# ad_1.net
KiCad netlist of a schematic drawn in Altium Designer
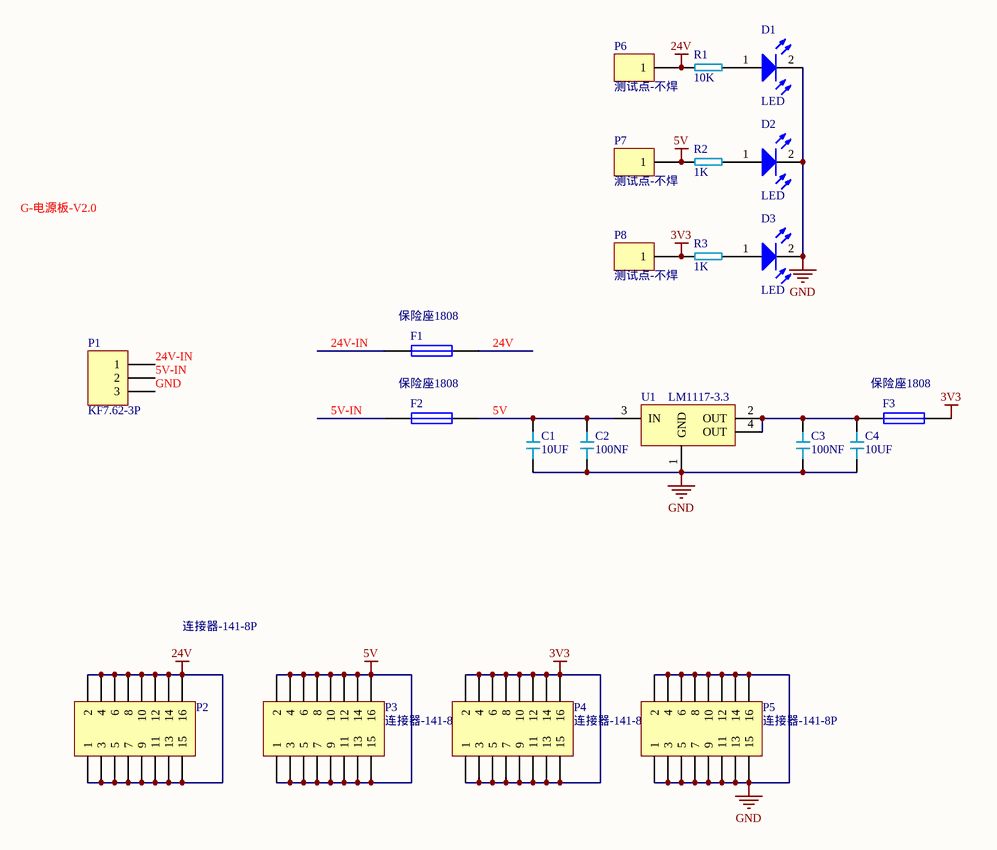
[diagram p0: ad_1.schdoc]

(export (version "E")
  (design (tool "Eeschema 10.0.6"))
  (components
    (comp (ref "C1")
      (value "10UF")
      (footprint "C0603")
      (description "贴片电容")
      (libsource (lib "base") (part "C0603"))
    )
    (comp (ref "C2")
      (value "100NF")
      (footprint "C0603")
      (description "贴片电容")
      (libsource (lib "base") (part "C0603"))
    )
    (comp (ref "C3")
      (value "100NF")
      (footprint "C0603")
      (description "贴片电容")
      (libsource (lib "base") (part "C0603"))
    )
    (comp (ref "C4")
      (value "10UF")
      (footprint "C0603")
      (description "贴片电容")
      (libsource (lib "base") (part "C0603"))
    )
    (comp (ref "D1")
      (value "LED")
      (footprint "LED0603")
      (description "LED0603")
      (fields (field (name "PUBLISHER") "Altium Limited"))
      (libsource (lib "base") (part "LED0603"))
    )
    (comp (ref "D2")
      (value "LED")
      (footprint "LED0603")
      (description "LED0603")
      (fields (field (name "PUBLISHER") "Altium Limited"))
      (libsource (lib "base") (part "LED0603"))
    )
    (comp (ref "D3")
      (value "LED")
      (footprint "LED0603")
      (description "LED0603")
      (fields (field (name "PUBLISHER") "Altium Limited"))
      (libsource (lib "base") (part "LED0603"))
    )
    (comp (ref "F1")
      (value "保险座1808")
      (footprint "F1808-ZUO")
      (description "保险座")
      (fields (field (name "PUBLISHER") "Altium Limited"))
      (libsource (lib "base") (part "Fuse0805"))
    )
    (comp (ref "F2")
      (value "保险座1808")
      (footprint "F1808-ZUO")
      (description "保险座")
      (fields (field (name "PUBLISHER") "Altium Limited"))
      (libsource (lib "base") (part "Fuse0805"))
    )
    (comp (ref "F3")
      (value "保险座1808")
      (footprint "F1808-ZUO")
      (description "保险座")
      (fields (field (name "PUBLISHER") "Altium Limited"))
      (libsource (lib "base") (part "Fuse0805"))
    )
    (comp (ref "P1")
      (value "KF7.62-3P")
      (footprint "KF7620-3P")
      (description "连接器")
      (fields (field (name "PUBLISHER") "Altium Limited"))
      (libsource (lib "base") (part "SIP3"))
    )
    (comp (ref "P2")
      (value "连接器-141-8P")
      (footprint "141V-8P")
      (description "连接器")
      (fields (field (name "PUBLISHER") "Altium Limited"))
      (libsource (lib "base") (part "DIC16"))
    )
    (comp (ref "P3")
      (value "连接器-141-8P")
      (footprint "141V-8P")
      (description "连接器")
      (fields (field (name "PUBLISHER") "Altium Limited"))
      (libsource (lib "base") (part "DIC16"))
    )
    (comp (ref "P4")
      (value "连接器-141-8P")
      (footprint "141V-8P")
      (description "连接器")
      (fields (field (name "PUBLISHER") "Altium Limited"))
      (libsource (lib "base") (part "DIC16"))
    )
    (comp (ref "P5")
      (value "连接器-141-8P")
      (footprint "141V-8P")
      (description "连接器")
      (fields (field (name "PUBLISHER") "Altium Limited"))
      (libsource (lib "base") (part "DIC16"))
    )
    (comp (ref "P6")
      (value "测试点-不焊")
      (footprint "test")
      (description "连接器")
      (fields (field (name "PUBLISHER") "Altium Limited"))
      (libsource (lib "base") (part "SIP1"))
    )
    (comp (ref "P7")
      (value "测试点-不焊")
      (footprint "test")
      (description "连接器")
      (fields (field (name "PUBLISHER") "Altium Limited"))
      (libsource (lib "base") (part "SIP1"))
    )
    (comp (ref "P8")
      (value "测试点-不焊")
      (footprint "test")
      (description "连接器")
      (fields (field (name "PUBLISHER") "Altium Limited"))
      (libsource (lib "base") (part "SIP1"))
    )
    (comp (ref "R1")
      (value "10K")
      (footprint "R0603")
      (description "贴片电阻")
      (libsource (lib "base") (part "R-0603"))
    )
    (comp (ref "R2")
      (value "1K")
      (footprint "R0603")
      (description "贴片电阻")
      (libsource (lib "base") (part "R-0603"))
    )
    (comp (ref "R3")
      (value "1K")
      (footprint "R0603")
      (description "贴片电阻")
      (libsource (lib "base") (part "R-0603"))
    )
    (comp (ref "U1")
      (value "LM1117-3.3")
      (footprint "SOT223")
      (description "芯片")
      (fields (field (name "PUBLISHER") "Altium Limited"))
      (libsource (lib "base") (part "1117"))
    )
  )
  (nets
    (net (code "1") (name "/5V-IN") (class "Default")
      (node (ref "F2") (pin "1") (pinfunction "1_1") (pintype "passive"))
      (node (ref "P1") (pin "2") (pinfunction "2_2") (pintype "passive"))
    )
    (net (code "2") (name "/24V-IN") (class "Default")
      (node (ref "F1") (pin "1") (pinfunction "1_1") (pintype "passive"))
      (node (ref "P1") (pin "1") (pinfunction "1_1") (pintype "passive"))
    )
    (net (code "4") (name "3V3") (class "Default")
      (node (ref "F3") (pin "2") (pinfunction "2_2") (pintype "passive"))
      (node (ref "P4") (pin "1") (pinfunction "1_1") (pintype "passive"))
      (node (ref "P4") (pin "10") (pinfunction "10_10") (pintype "passive"))
      (node (ref "P4") (pin "11") (pinfunction "11_11") (pintype "passive"))
      (node (ref "P4") (pin "12") (pinfunction "12_12") (pintype "passive"))
      (node (ref "P4") (pin "13") (pinfunction "13_13") (pintype "passive"))
      (node (ref "P4") (pin "14") (pinfunction "14_14") (pintype "passive"))
      (node (ref "P4") (pin "15") (pinfunction "15_15") (pintype "passive"))
      (node (ref "P4") (pin "16") (pinfunction "16_16") (pintype "passive"))
      (node (ref "P4") (pin "2") (pinfunction "2_2") (pintype "passive"))
      (node (ref "P4") (pin "3") (pinfunction "3_3") (pintype "passive"))
      (node (ref "P4") (pin "4") (pinfunction "4_4") (pintype "passive"))
      (node (ref "P4") (pin "5") (pinfunction "5_5") (pintype "passive"))
      (node (ref "P4") (pin "6") (pinfunction "6_6") (pintype "passive"))
      (node (ref "P4") (pin "7") (pinfunction "7_7") (pintype "passive"))
      (node (ref "P4") (pin "8") (pinfunction "8_8") (pintype "passive"))
      (node (ref "P4") (pin "9") (pinfunction "9_9") (pintype "passive"))
      (node (ref "P8") (pin "1") (pinfunction "1_1") (pintype "passive"))
      (node (ref "R3") (pin "1") (pinfunction "1_1") (pintype "passive"))
    )
    (net (code "5") (name "5V") (class "Default")
      (node (ref "C1") (pin "2") (pinfunction "2_2") (pintype "passive"))
      (node (ref "C2") (pin "2") (pinfunction "2_2") (pintype "passive"))
      (node (ref "F2") (pin "2") (pinfunction "2_2") (pintype "passive"))
      (node (ref "P3") (pin "1") (pinfunction "1_1") (pintype "passive"))
      (node (ref "P3") (pin "10") (pinfunction "10_10") (pintype "passive"))
      (node (ref "P3") (pin "11") (pinfunction "11_11") (pintype "passive"))
      (node (ref "P3") (pin "12") (pinfunction "12_12") (pintype "passive"))
      (node (ref "P3") (pin "13") (pinfunction "13_13") (pintype "passive"))
      (node (ref "P3") (pin "14") (pinfunction "14_14") (pintype "passive"))
      (node (ref "P3") (pin "15") (pinfunction "15_15") (pintype "passive"))
      (node (ref "P3") (pin "16") (pinfunction "16_16") (pintype "passive"))
      (node (ref "P3") (pin "2") (pinfunction "2_2") (pintype "passive"))
      (node (ref "P3") (pin "3") (pinfunction "3_3") (pintype "passive"))
      (node (ref "P3") (pin "4") (pinfunction "4_4") (pintype "passive"))
      (node (ref "P3") (pin "5") (pinfunction "5_5") (pintype "passive"))
      (node (ref "P3") (pin "6") (pinfunction "6_6") (pintype "passive"))
      (node (ref "P3") (pin "7") (pinfunction "7_7") (pintype "passive"))
      (node (ref "P3") (pin "8") (pinfunction "8_8") (pintype "passive"))
      (node (ref "P3") (pin "9") (pinfunction "9_9") (pintype "passive"))
      (node (ref "P7") (pin "1") (pinfunction "1_1") (pintype "passive"))
      (node (ref "R2") (pin "1") (pinfunction "1_1") (pintype "passive"))
      (node (ref "U1") (pin "3") (pinfunction "IN_3") (pintype "passive"))
    )
    (net (code "6") (name "24V") (class "Default")
      (node (ref "F1") (pin "2") (pinfunction "2_2") (pintype "passive"))
      (node (ref "P2") (pin "1") (pinfunction "1_1") (pintype "passive"))
      (node (ref "P2") (pin "10") (pinfunction "10_10") (pintype "passive"))
      (node (ref "P2") (pin "11") (pinfunction "11_11") (pintype "passive"))
      (node (ref "P2") (pin "12") (pinfunction "12_12") (pintype "passive"))
      (node (ref "P2") (pin "13") (pinfunction "13_13") (pintype "passive"))
      (node (ref "P2") (pin "14") (pinfunction "14_14") (pintype "passive"))
      (node (ref "P2") (pin "15") (pinfunction "15_15") (pintype "passive"))
      (node (ref "P2") (pin "16") (pinfunction "16_16") (pintype "passive"))
      (node (ref "P2") (pin "2") (pinfunction "2_2") (pintype "passive"))
      (node (ref "P2") (pin "3") (pinfunction "3_3") (pintype "passive"))
      (node (ref "P2") (pin "4") (pinfunction "4_4") (pintype "passive"))
      (node (ref "P2") (pin "5") (pinfunction "5_5") (pintype "passive"))
      (node (ref "P2") (pin "6") (pinfunction "6_6") (pintype "passive"))
      (node (ref "P2") (pin "7") (pinfunction "7_7") (pintype "passive"))
      (node (ref "P2") (pin "8") (pinfunction "8_8") (pintype "passive"))
      (node (ref "P2") (pin "9") (pinfunction "9_9") (pintype "passive"))
      (node (ref "P6") (pin "1") (pinfunction "1_1") (pintype "passive"))
      (node (ref "R1") (pin "1") (pinfunction "1_1") (pintype "passive"))
    )
    (net (code "7") (name "GND") (class "Default")
      (node (ref "C1") (pin "1") (pinfunction "1_1") (pintype "passive"))
      (node (ref "C2") (pin "1") (pinfunction "1_1") (pintype "passive"))
      (node (ref "C3") (pin "1") (pinfunction "1_1") (pintype "passive"))
      (node (ref "C4") (pin "1") (pinfunction "1_1") (pintype "passive"))
      (node (ref "D1") (pin "2") (pinfunction "K_2") (pintype "passive"))
      (node (ref "D2") (pin "2") (pinfunction "K_2") (pintype "passive"))
      (node (ref "D3") (pin "2") (pinfunction "K_2") (pintype "passive"))
      (node (ref "P1") (pin "3") (pinfunction "3_3") (pintype "passive"))
      (node (ref "P5") (pin "1") (pinfunction "1_1") (pintype "passive"))
      (node (ref "P5") (pin "10") (pinfunction "10_10") (pintype "passive"))
      (node (ref "P5") (pin "11") (pinfunction "11_11") (pintype "passive"))
      (node (ref "P5") (pin "12") (pinfunction "12_12") (pintype "passive"))
      (node (ref "P5") (pin "13") (pinfunction "13_13") (pintype "passive"))
      (node (ref "P5") (pin "14") (pinfunction "14_14") (pintype "passive"))
      (node (ref "P5") (pin "15") (pinfunction "15_15") (pintype "passive"))
      (node (ref "P5") (pin "16") (pinfunction "16_16") (pintype "passive"))
      (node (ref "P5") (pin "2") (pinfunction "2_2") (pintype "passive"))
      (node (ref "P5") (pin "3") (pinfunction "3_3") (pintype "passive"))
      (node (ref "P5") (pin "4") (pinfunction "4_4") (pintype "passive"))
      (node (ref "P5") (pin "5") (pinfunction "5_5") (pintype "passive"))
      (node (ref "P5") (pin "6") (pinfunction "6_6") (pintype "passive"))
      (node (ref "P5") (pin "7") (pinfunction "7_7") (pintype "passive"))
      (node (ref "P5") (pin "8") (pinfunction "8_8") (pintype "passive"))
      (node (ref "P5") (pin "9") (pinfunction "9_9") (pintype "passive"))
      (node (ref "U1") (pin "1") (pinfunction "GND_1") (pintype "passive"))
    )
    (net (code "8") (name "Net-(C3-Pad2)") (class "Default")
      (node (ref "C3") (pin "2") (pinfunction "2_2") (pintype "passive"))
      (node (ref "C4") (pin "2") (pinfunction "2_2") (pintype "passive"))
      (node (ref "F3") (pin "1") (pinfunction "1_1") (pintype "passive"))
      (node (ref "U1") (pin "2") (pinfunction "OUT_2") (pintype "passive"))
      (node (ref "U1") (pin "4") (pinfunction "OUT_4") (pintype "passive"))
    )
    (net (code "9") (name "Net-(D1-A)") (class "Default")
      (node (ref "D1") (pin "1") (pinfunction "A_1") (pintype "passive"))
      (node (ref "R1") (pin "2") (pinfunction "2_2") (pintype "passive"))
    )
    (net (code "10") (name "Net-(D2-A)") (class "Default")
      (node (ref "D2") (pin "1") (pinfunction "A_1") (pintype "passive"))
      (node (ref "R2") (pin "2") (pinfunction "2_2") (pintype "passive"))
    )
    (net (code "11") (name "Net-(D3-A)") (class "Default")
      (node (ref "D3") (pin "1") (pinfunction "A_1") (pintype "passive"))
      (node (ref "R3") (pin "2") (pinfunction "2_2") (pintype "passive"))
    )
  )
)
